# untitled.net
KiCad netlist of a schematic drawn in EAGLE
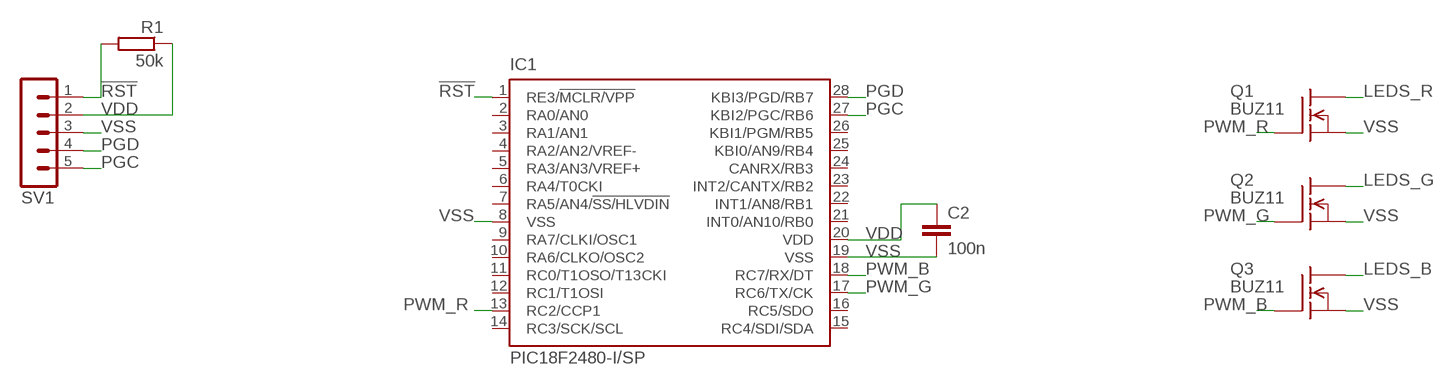
[diagram p0: schematic, sheet 1]

(export (version "E")
  (design (tool "Eeschema 10.0.6"))
  (components
    (comp (ref "C2")
      (value "100n")
      (footprint "eagle-import:C050-024X044")
      (libsource (lib "eagle-import") (part "C-EU050-024X044"))
    )
    (comp (ref "IC1")
      (value "PIC18F2480-I/SP")
      (footprint "eagle-import:DIL28-3")
      (fields (field (name "MF") "MICROCHIP"))
      (libsource (lib "eagle-import") (part "PIC18F280-I/SP4"))
    )
    (comp (ref "Q1")
      (value "BUZ11")
      (footprint "eagle-import:TO220")
      (libsource (lib "eagle-import") (part "BUZ11"))
    )
    (comp (ref "Q2")
      (value "BUZ11")
      (footprint "eagle-import:TO220")
      (libsource (lib "eagle-import") (part "BUZ11"))
    )
    (comp (ref "Q3")
      (value "BUZ11")
      (footprint "eagle-import:TO220")
      (libsource (lib "eagle-import") (part "BUZ11"))
    )
    (comp (ref "R1")
      (value "50k")
      (footprint "eagle-import:0207_10")
      (libsource (lib "eagle-import") (part "R-EU_0207/10"))
    )
    (comp (ref "SV1")
      (value "MA05-1")
      (footprint "eagle-import:MA05-1")
      (libsource (lib "eagle-import") (part "MA05-1"))
    )
  )
  (nets
    (net (code "1") (name "/LEDS_B") (class "Default")
      (node (ref "Q3") (pin "2") (pinfunction "D_2") (pintype "passive"))
    )
    (net (code "2") (name "/LEDS_G") (class "Default")
      (node (ref "Q2") (pin "2") (pinfunction "D_2") (pintype "passive"))
    )
    (net (code "3") (name "/LEDS_R") (class "Default")
      (node (ref "Q1") (pin "2") (pinfunction "D_2") (pintype "passive"))
    )
    (net (code "4") (name "/PGC") (class "Default")
      (node (ref "IC1") (pin "27") (pinfunction "KBI2/PGC/RB6_27") (pintype "bidirectional"))
      (node (ref "SV1") (pin "5") (pinfunction "5_5") (pintype "passive"))
    )
    (net (code "5") (name "/PGD") (class "Default")
      (node (ref "IC1") (pin "28") (pinfunction "KBI3/PGD/RB7_28") (pintype "bidirectional"))
      (node (ref "SV1") (pin "4") (pinfunction "4_4") (pintype "passive"))
    )
    (net (code "6") (name "/PWM_B") (class "Default")
      (node (ref "IC1") (pin "18") (pinfunction "RC7/RX/DT_18") (pintype "bidirectional"))
      (node (ref "Q3") (pin "1") (pinfunction "G_1") (pintype "passive"))
    )
    (net (code "7") (name "/PWM_G") (class "Default")
      (node (ref "IC1") (pin "17") (pinfunction "RC6/TX/CK_17") (pintype "bidirectional"))
      (node (ref "Q2") (pin "1") (pinfunction "G_1") (pintype "passive"))
    )
    (net (code "8") (name "/PWM_R") (class "Default")
      (node (ref "IC1") (pin "13") (pinfunction "RC2/CCP1_13") (pintype "bidirectional"))
      (node (ref "Q1") (pin "1") (pinfunction "G_1") (pintype "passive"))
    )
    (net (code "9") (name "/VDD") (class "Default")
      (node (ref "C2") (pin "1") (pinfunction "1_1") (pintype "passive"))
      (node (ref "IC1") (pin "20") (pinfunction "VDD_20") (pintype "power_in"))
      (node (ref "R1") (pin "1") (pinfunction "1_1") (pintype "passive"))
      (node (ref "SV1") (pin "2") (pinfunction "2_2") (pintype "passive"))
    )
    (net (code "10") (name "/VSS") (class "Default")
      (node (ref "C2") (pin "2") (pinfunction "2_2") (pintype "passive"))
      (node (ref "IC1") (pin "19") (pinfunction "VSS_19") (pintype "power_in"))
      (node (ref "IC1") (pin "8") (pinfunction "VSS_8") (pintype "power_in"))
      (node (ref "Q1") (pin "3") (pinfunction "S_3") (pintype "passive"))
      (node (ref "Q2") (pin "3") (pinfunction "S_3") (pintype "passive"))
      (node (ref "Q3") (pin "3") (pinfunction "S_3") (pintype "passive"))
      (node (ref "SV1") (pin "3") (pinfunction "3_3") (pintype "passive"))
    )
    (net (code "11") (name "/~{RST}") (class "Default")
      (node (ref "IC1") (pin "1") (pinfunction "RE3/~{MCLR/VPP}_1") (pintype "input"))
      (node (ref "R1") (pin "2") (pinfunction "2_2") (pintype "passive"))
      (node (ref "SV1") (pin "1") (pinfunction "1_1") (pintype "passive"))
    )
    (net (code "12") (name "unconnected-(IC1-CANRX{slash}RB3-Pad24)") (class "Default")
      (node (ref "IC1") (pin "24") (pinfunction "CANRX/RB3_24") (pintype "bidirectional"))
    )
    (net (code "13") (name "unconnected-(IC1-INT0{slash}AN10{slash}RB0-Pad21)") (class "Default")
      (node (ref "IC1") (pin "21") (pinfunction "INT0/AN10/RB0_21") (pintype "bidirectional"))
    )
    (net (code "14") (name "unconnected-(IC1-INT1{slash}AN8{slash}RB1-Pad22)") (class "Default")
      (node (ref "IC1") (pin "22") (pinfunction "INT1/AN8/RB1_22") (pintype "bidirectional"))
    )
    (net (code "15") (name "unconnected-(IC1-INT2{slash}CANTX{slash}RB2-Pad23)") (class "Default")
      (node (ref "IC1") (pin "23") (pinfunction "INT2/CANTX/RB2_23") (pintype "bidirectional"))
    )
    (net (code "16") (name "unconnected-(IC1-KBI0{slash}AN9{slash}RB4-Pad25)") (class "Default")
      (node (ref "IC1") (pin "25") (pinfunction "KBI0/AN9/RB4_25") (pintype "bidirectional"))
    )
    (net (code "17") (name "unconnected-(IC1-KBI1{slash}PGM{slash}RB5-Pad26)") (class "Default")
      (node (ref "IC1") (pin "26") (pinfunction "KBI1/PGM/RB5_26") (pintype "bidirectional"))
    )
    (net (code "18") (name "unconnected-(IC1-RA0{slash}AN0-Pad2)") (class "Default")
      (node (ref "IC1") (pin "2") (pinfunction "RA0/AN0_2") (pintype "bidirectional"))
    )
    (net (code "19") (name "unconnected-(IC1-RA1{slash}AN1-Pad3)") (class "Default")
      (node (ref "IC1") (pin "3") (pinfunction "RA1/AN1_3") (pintype "bidirectional"))
    )
    (net (code "20") (name "unconnected-(IC1-RA2{slash}AN2{slash}VREF--Pad4)") (class "Default")
      (node (ref "IC1") (pin "4") (pinfunction "RA2/AN2/VREF-_4") (pintype "bidirectional"))
    )
    (net (code "21") (name "unconnected-(IC1-RA3{slash}AN3{slash}VREF+-Pad5)") (class "Default")
      (node (ref "IC1") (pin "5") (pinfunction "RA3/AN3/VREF+_5") (pintype "bidirectional"))
    )
    (net (code "22") (name "unconnected-(IC1-RA4{slash}T0CKI-Pad6)") (class "Default")
      (node (ref "IC1") (pin "6") (pinfunction "RA4/T0CKI_6") (pintype "bidirectional"))
    )
    (net (code "23") (name "unconnected-(IC1-RA5{slash}AN4{slash}~{SS{slash}HLVDIN}-Pad7)") (class "Default")
      (node (ref "IC1") (pin "7") (pinfunction "RA5/AN4/~{SS/HLVDIN}_7") (pintype "bidirectional"))
    )
    (net (code "24") (name "unconnected-(IC1-RA6{slash}CLKO{slash}OSC2-Pad10)") (class "Default")
      (node (ref "IC1") (pin "10") (pinfunction "RA6/CLKO/OSC2_10") (pintype "output"))
    )
    (net (code "25") (name "unconnected-(IC1-RA7{slash}CLKI{slash}OSC1-Pad9)") (class "Default")
      (node (ref "IC1") (pin "9") (pinfunction "RA7/CLKI/OSC1_9") (pintype "input"))
    )
    (net (code "26") (name "unconnected-(IC1-RC0{slash}T1OSO{slash}T13CKI-Pad11)") (class "Default")
      (node (ref "IC1") (pin "11") (pinfunction "RC0/T1OSO/T13CKI_11") (pintype "bidirectional"))
    )
    (net (code "27") (name "unconnected-(IC1-RC1{slash}T1OSI-Pad12)") (class "Default")
      (node (ref "IC1") (pin "12") (pinfunction "RC1/T1OSI_12") (pintype "bidirectional"))
    )
    (net (code "28") (name "unconnected-(IC1-RC3{slash}SCK{slash}SCL-Pad14)") (class "Default")
      (node (ref "IC1") (pin "14") (pinfunction "RC3/SCK/SCL_14") (pintype "bidirectional"))
    )
    (net (code "29") (name "unconnected-(IC1-RC4{slash}SDI{slash}SDA-Pad15)") (class "Default")
      (node (ref "IC1") (pin "15") (pinfunction "RC4/SDI/SDA_15") (pintype "bidirectional"))
    )
    (net (code "30") (name "unconnected-(IC1-RC5{slash}SDO-Pad16)") (class "Default")
      (node (ref "IC1") (pin "16") (pinfunction "RC5/SDO_16") (pintype "bidirectional"))
    )
  )
)
